# MainBoard.net
KiCad netlist of a schematic drawn in EAGLE
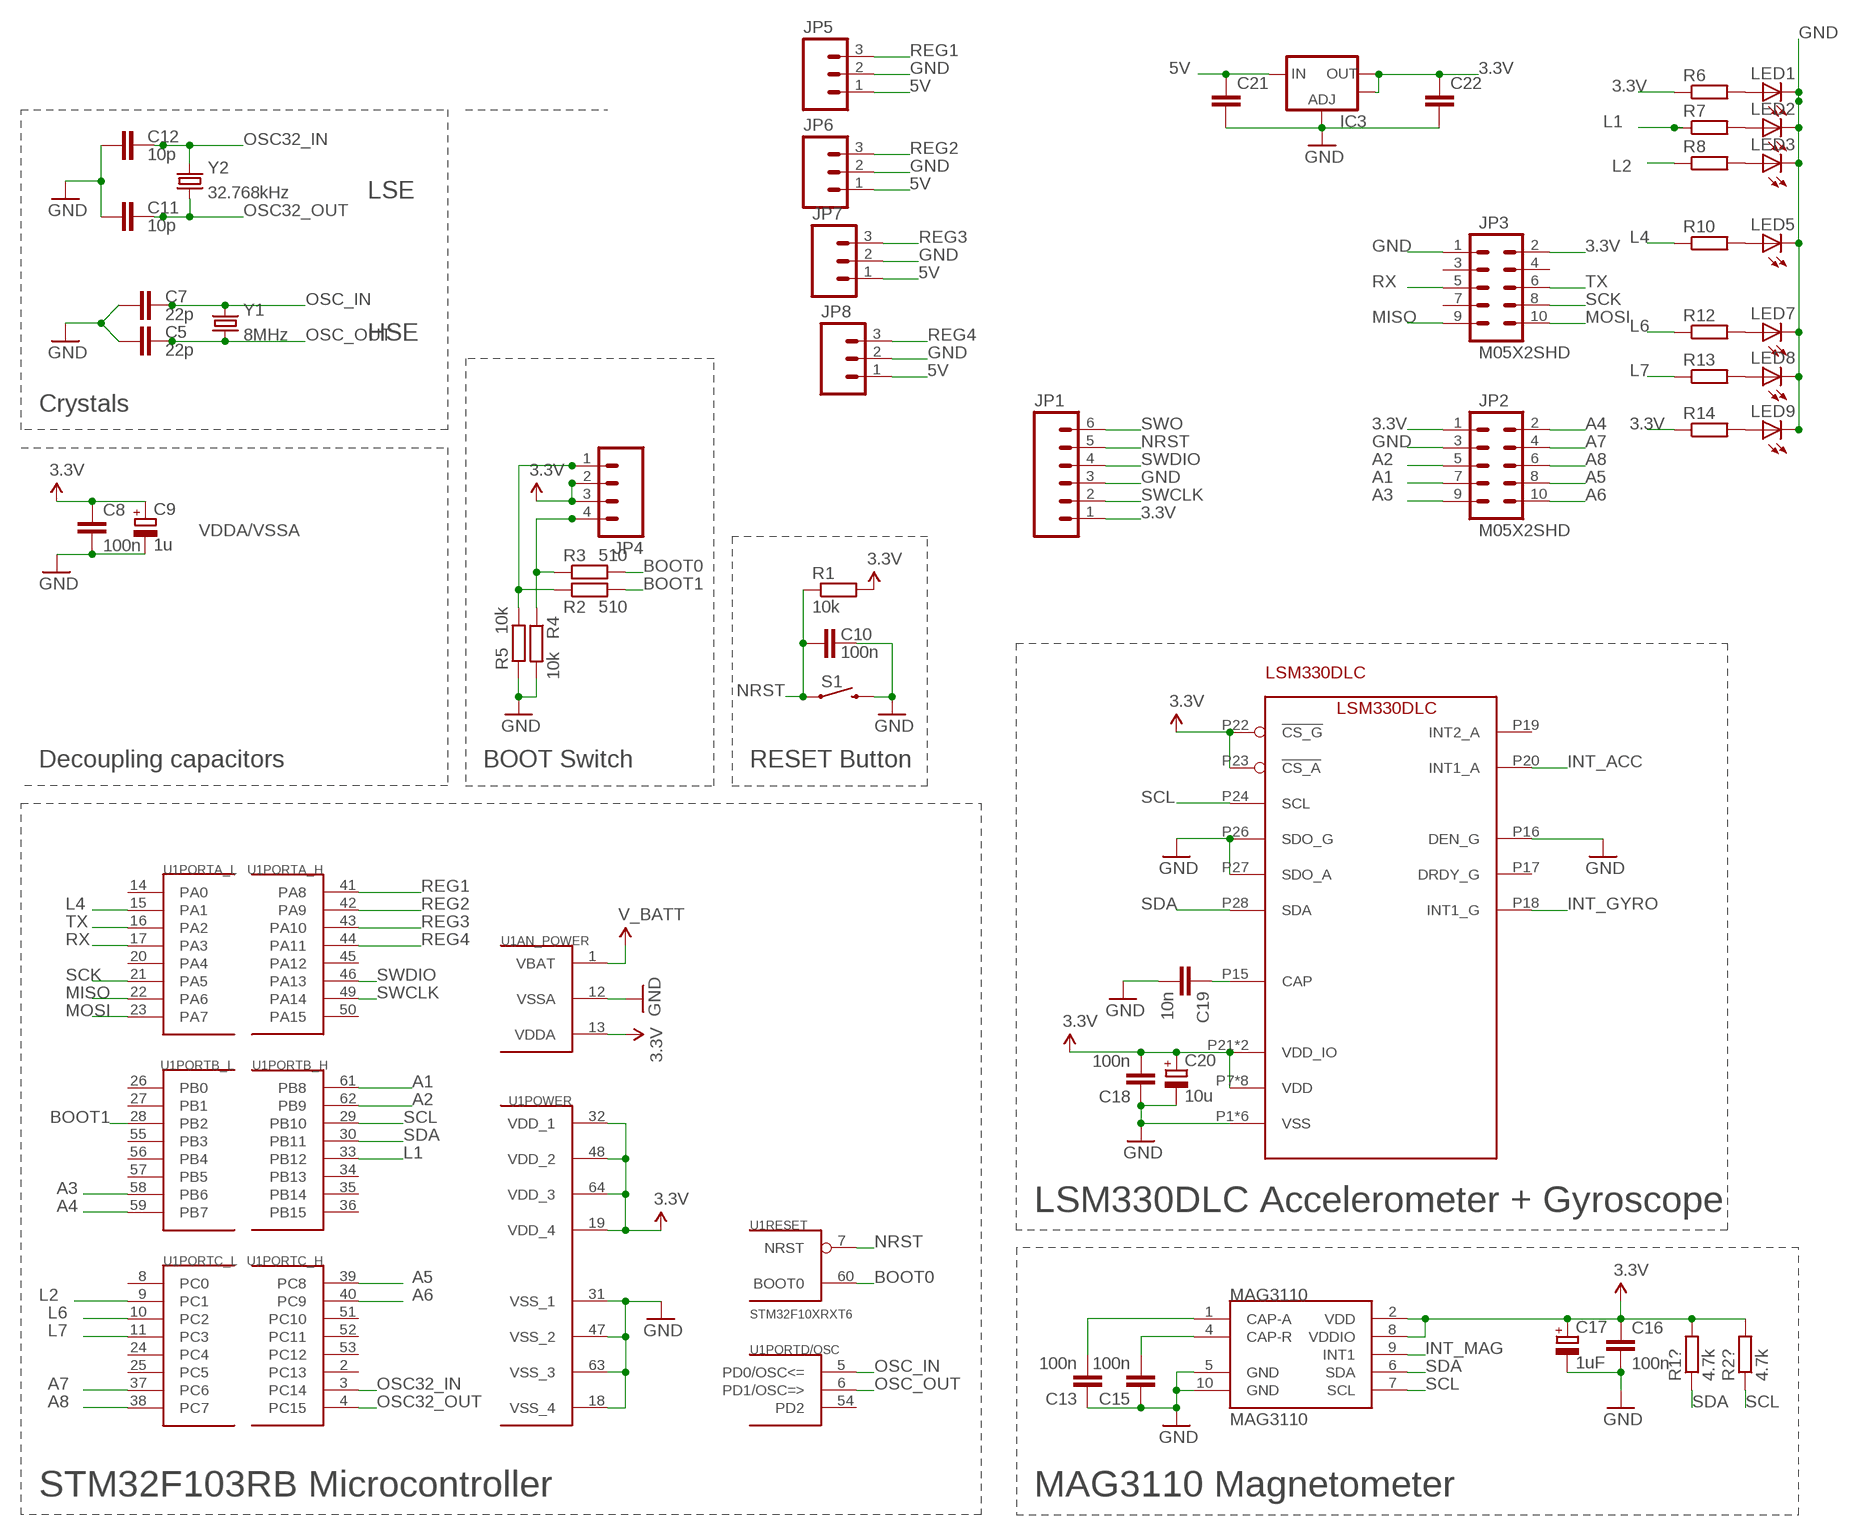
[diagram p0: schematic, sheet 1]

(export (version "E")
  (design (tool "Eeschema 10.0.6"))
  (components
    (comp (ref "C5")
      (value "22p")
      (footprint "eagle-import:C0805")
      (libsource (lib "eagle-import") (part "C-EUC0805"))
    )
    (comp (ref "C7")
      (value "22p")
      (footprint "eagle-import:C0805")
      (libsource (lib "eagle-import") (part "C-EUC0805"))
    )
    (comp (ref "C8")
      (value "100n")
      (footprint "eagle-import:C0805")
      (libsource (lib "eagle-import") (part "C-EUC0805"))
    )
    (comp (ref "C9")
      (value "1u")
      (footprint "eagle-import:SMC_A")
      (libsource (lib "eagle-import") (part "CPOL-EUSMCA"))
    )
    (comp (ref "C10")
      (value "100n")
      (footprint "eagle-import:C0805")
      (libsource (lib "eagle-import") (part "C-EUC0805"))
    )
    (comp (ref "C11")
      (value "10p")
      (footprint "eagle-import:C0805")
      (libsource (lib "eagle-import") (part "C-EUC0805"))
    )
    (comp (ref "C12")
      (value "10p")
      (footprint "eagle-import:C0805")
      (libsource (lib "eagle-import") (part "C-EUC0805"))
    )
    (comp (ref "C13")
      (value "100n")
      (footprint "eagle-import:C0805")
      (libsource (lib "eagle-import") (part "C-EUC0805"))
    )
    (comp (ref "C15")
      (value "100n")
      (footprint "eagle-import:C0805")
      (libsource (lib "eagle-import") (part "C-EUC0805"))
    )
    (comp (ref "C16")
      (value "100n")
      (footprint "eagle-import:C0805")
      (libsource (lib "eagle-import") (part "C-EUC0805"))
    )
    (comp (ref "C17")
      (value "1uF")
      (footprint "eagle-import:SMC_A")
      (libsource (lib "eagle-import") (part "CPOL-EUSMCA"))
    )
    (comp (ref "C18")
      (value "100n")
      (footprint "eagle-import:C0805")
      (libsource (lib "eagle-import") (part "resistor_C-EUC0805"))
    )
    (comp (ref "C19")
      (value "10n")
      (footprint "eagle-import:C0805")
      (libsource (lib "eagle-import") (part "resistor_C-EUC0805"))
    )
    (comp (ref "C20")
      (value "10u")
      (footprint "eagle-import:SMC_A")
      (libsource (lib "eagle-import") (part "CPOL-EUSMCA"))
    )
    (comp (ref "C21")
      (value "C-EUC0805")
      (footprint "eagle-import:C0805")
      (libsource (lib "eagle-import") (part "C-EUC0805"))
    )
    (comp (ref "C22")
      (value "C-EUC0805")
      (footprint "eagle-import:C0805")
      (libsource (lib "eagle-import") (part "C-EUC0805"))
    )
    (comp (ref "IC3")
      (value "V_REG_LM1117SOT223")
      (footprint "eagle-import:SOT223")
      (libsource (lib "eagle-import") (part "V_REG_LM1117SOT223"))
    )
    (comp (ref "JP1")
      (value "M06LONGPADS")
      (footprint "eagle-import:1X06_LONGPADS")
      (libsource (lib "eagle-import") (part "M06LONGPADS"))
    )
    (comp (ref "JP2")
      (value "M05X2SHD")
      (footprint "eagle-import:2X5-SHROUDED")
      (libsource (lib "eagle-import") (part "M05X2SHD"))
    )
    (comp (ref "JP3")
      (value "M05X2SHD")
      (footprint "eagle-import:2X5-SHROUDED")
      (libsource (lib "eagle-import") (part "M05X2SHD"))
    )
    (comp (ref "JP4")
      (value "M04LONGPADS")
      (footprint "eagle-import:1X04_LONGPADS")
      (libsource (lib "eagle-import") (part "M04LONGPADS"))
    )
    (comp (ref "JP5")
      (value "M03LONGPADS")
      (footprint "eagle-import:1X03_LONGPADS")
      (libsource (lib "eagle-import") (part "M03LONGPADS"))
    )
    (comp (ref "JP6")
      (value "M03LONGPADS")
      (footprint "eagle-import:1X03_LONGPADS")
      (libsource (lib "eagle-import") (part "M03LONGPADS"))
    )
    (comp (ref "JP7")
      (value "M03LONGPADS")
      (footprint "eagle-import:1X03_LONGPADS")
      (libsource (lib "eagle-import") (part "M03LONGPADS"))
    )
    (comp (ref "JP8")
      (value "M03LONGPADS")
      (footprint "eagle-import:1X03_LONGPADS")
      (libsource (lib "eagle-import") (part "M03LONGPADS"))
    )
    (comp (ref "LED1")
      (value "LEDCHIPLED_0805")
      (footprint "eagle-import:CHIPLED_0805")
      (libsource (lib "eagle-import") (part "LEDCHIPLED_0805"))
    )
    (comp (ref "LED2")
      (value "LEDCHIPLED_0805")
      (footprint "eagle-import:CHIPLED_0805")
      (libsource (lib "eagle-import") (part "LEDCHIPLED_0805"))
    )
    (comp (ref "LED3")
      (value "LEDCHIPLED_0805")
      (footprint "eagle-import:CHIPLED_0805")
      (libsource (lib "eagle-import") (part "LEDCHIPLED_0805"))
    )
    (comp (ref "LED5")
      (value "LEDCHIPLED_0805")
      (footprint "eagle-import:CHIPLED_0805")
      (libsource (lib "eagle-import") (part "LEDCHIPLED_0805"))
    )
    (comp (ref "LED7")
      (value "LEDCHIPLED_0805")
      (footprint "eagle-import:CHIPLED_0805")
      (libsource (lib "eagle-import") (part "LEDCHIPLED_0805"))
    )
    (comp (ref "LED8")
      (value "LEDCHIPLED_0805")
      (footprint "eagle-import:CHIPLED_0805")
      (libsource (lib "eagle-import") (part "LEDCHIPLED_0805"))
    )
    (comp (ref "LED9")
      (value "LEDCHIPLED_0805")
      (footprint "eagle-import:CHIPLED_0805")
      (libsource (lib "eagle-import") (part "LEDCHIPLED_0805"))
    )
    (comp (ref "LSM330DLC")
      (value "LSM330DLC")
      (footprint "eagle-import:LGA_4X5X1P1_28L")
      (libsource (lib "eagle-import") (part "LSM330DLC"))
    )
    (comp (ref "MAG3110")
      (value "MAG3110")
      (footprint "eagle-import:DFN-10")
      (libsource (lib "eagle-import") (part "MAG3110"))
    )
    (comp (ref "R1")
      (value "10k")
      (footprint "eagle-import:R0805")
      (libsource (lib "eagle-import") (part "R-EU_R0805"))
    )
    (comp (ref "R1?")
      (value "4.7k")
      (footprint "eagle-import:R0805")
      (libsource (lib "eagle-import") (part "R-EU_R0805"))
    )
    (comp (ref "R2")
      (value "510")
      (footprint "eagle-import:R0805")
      (libsource (lib "eagle-import") (part "R-EU_R0805"))
    )
    (comp (ref "R2?")
      (value "4.7k")
      (footprint "eagle-import:R0805")
      (libsource (lib "eagle-import") (part "R-EU_R0805"))
    )
    (comp (ref "R3")
      (value "510")
      (footprint "eagle-import:R0805")
      (libsource (lib "eagle-import") (part "R-EU_R0805"))
    )
    (comp (ref "R4")
      (value "10k")
      (footprint "eagle-import:R0805")
      (libsource (lib "eagle-import") (part "R-EU_R0805"))
    )
    (comp (ref "R5")
      (value "10k")
      (footprint "eagle-import:R0805")
      (libsource (lib "eagle-import") (part "R-EU_R0805"))
    )
    (comp (ref "R6")
      (value "R-EU_M0805")
      (footprint "eagle-import:M0805")
      (libsource (lib "eagle-import") (part "resistor_R-EU_M0805"))
    )
    (comp (ref "R7")
      (value "R-EU_M0805")
      (footprint "eagle-import:M0805")
      (libsource (lib "eagle-import") (part "resistor_R-EU_M0805"))
    )
    (comp (ref "R8")
      (value "R-EU_M0805")
      (footprint "eagle-import:M0805")
      (libsource (lib "eagle-import") (part "resistor_R-EU_M0805"))
    )
    (comp (ref "R10")
      (value "R-EU_M0805")
      (footprint "eagle-import:M0805")
      (libsource (lib "eagle-import") (part "resistor_R-EU_M0805"))
    )
    (comp (ref "R12")
      (value "R-EU_M0805")
      (footprint "eagle-import:M0805")
      (libsource (lib "eagle-import") (part "resistor_R-EU_M0805"))
    )
    (comp (ref "R13")
      (value "R-EU_M0805")
      (footprint "eagle-import:M0805")
      (libsource (lib "eagle-import") (part "resistor_R-EU_M0805"))
    )
    (comp (ref "R14")
      (value "R-EU_M0805")
      (footprint "eagle-import:M0805")
      (libsource (lib "eagle-import") (part "resistor_R-EU_M0805"))
    )
    (comp (ref "S1")
      (value "SWITCH-MOMENTARY-2-SMD-1101NE")
      (footprint "eagle-import:TACTILE-SWITCH-1101NE")
      (libsource (lib "eagle-import") (part "SWITCH-MOMENTARY-2-SMD-1101NE"))
    )
    (comp (ref "U1")
      (value "STM32F10XRXT6")
      (footprint "eagle-import:TQFP64")
      (libsource (lib "eagle-import") (part "STM32F10XRXT6"))
    )
    (comp (ref "Y1")
      (value "8MHz")
      (footprint "eagle-import:HC49UP")
      (libsource (lib "eagle-import") (part "CRYSTALSMD"))
    )
    (comp (ref "Y2")
      (value "32.768kHz")
      (footprint "eagle-import:CRYSTAL-32KHZ-SMD_EPSON_MC146")
      (libsource (lib "eagle-import") (part "CRYSTALEPSONMC146"))
    )
  )
  (nets
    (net (code "1") (name "/5V") (class "Default")
      (node (ref "C21") (pin "1") (pinfunction "1_1") (pintype "passive"))
      (node (ref "IC3") (pin "3") (pinfunction "IN_3") (pintype "input"))
      (node (ref "JP5") (pin "1") (pinfunction "1_1") (pintype "passive"))
      (node (ref "JP6") (pin "1") (pinfunction "1_1") (pintype "passive"))
      (node (ref "JP7") (pin "1") (pinfunction "1_1") (pintype "passive"))
      (node (ref "JP8") (pin "1") (pinfunction "1_1") (pintype "passive"))
    )
    (net (code "2") (name "/A1") (class "Default")
      (node (ref "JP2") (pin "7") (pinfunction "7_7") (pintype "passive"))
      (node (ref "U1") (pin "61") (pinfunction "PB8_61") (pintype "bidirectional"))
    )
    (net (code "3") (name "/A2") (class "Default")
      (node (ref "JP2") (pin "5") (pinfunction "5_5") (pintype "passive"))
      (node (ref "U1") (pin "62") (pinfunction "PB9_62") (pintype "bidirectional"))
    )
    (net (code "4") (name "/A3") (class "Default")
      (node (ref "JP2") (pin "9") (pinfunction "9_9") (pintype "passive"))
      (node (ref "U1") (pin "58") (pinfunction "PB6_58") (pintype "bidirectional"))
    )
    (net (code "5") (name "/A4") (class "Default")
      (node (ref "JP2") (pin "2") (pinfunction "2_2") (pintype "passive"))
      (node (ref "U1") (pin "59") (pinfunction "PB7_59") (pintype "bidirectional"))
    )
    (net (code "6") (name "/A5") (class "Default")
      (node (ref "JP2") (pin "8") (pinfunction "8_8") (pintype "passive"))
      (node (ref "U1") (pin "39") (pinfunction "PC8_39") (pintype "bidirectional"))
    )
    (net (code "7") (name "/A6") (class "Default")
      (node (ref "JP2") (pin "10") (pinfunction "10_10") (pintype "passive"))
      (node (ref "U1") (pin "40") (pinfunction "PC9_40") (pintype "bidirectional"))
    )
    (net (code "8") (name "/A7") (class "Default")
      (node (ref "JP2") (pin "4") (pinfunction "4_4") (pintype "passive"))
      (node (ref "U1") (pin "37") (pinfunction "PC6_37") (pintype "bidirectional"))
    )
    (net (code "9") (name "/A8") (class "Default")
      (node (ref "JP2") (pin "6") (pinfunction "6_6") (pintype "passive"))
      (node (ref "U1") (pin "38") (pinfunction "PC7_38") (pintype "bidirectional"))
    )
    (net (code "10") (name "/BOOT0") (class "Default")
      (node (ref "R3") (pin "2") (pinfunction "2_2") (pintype "passive"))
      (node (ref "U1") (pin "60") (pinfunction "BOOT0_60") (pintype "input"))
    )
    (net (code "11") (name "/BOOT1") (class "Default")
      (node (ref "R2") (pin "2") (pinfunction "2_2") (pintype "passive"))
      (node (ref "U1") (pin "28") (pinfunction "PB2_28") (pintype "bidirectional"))
    )
    (net (code "12") (name "/INT_ACC") (class "Default")
      (node (ref "LSM330DLC") (pin "P20") (pinfunction "INT1_A_P20") (pintype "output"))
    )
    (net (code "13") (name "/INT_GYRO") (class "Default")
      (node (ref "LSM330DLC") (pin "P18") (pinfunction "INT1_G_P18") (pintype "output"))
    )
    (net (code "14") (name "/INT_MAG") (class "Default")
      (node (ref "MAG3110") (pin "9") (pinfunction "INT1_9") (pintype "bidirectional"))
    )
    (net (code "15") (name "/L1") (class "Default")
      (node (ref "R7") (pin "1") (pinfunction "1_1") (pintype "passive"))
      (node (ref "U1") (pin "33") (pinfunction "PB12_33") (pintype "bidirectional"))
    )
    (net (code "16") (name "/L2") (class "Default")
      (node (ref "R8") (pin "1") (pinfunction "1_1") (pintype "passive"))
      (node (ref "U1") (pin "9") (pinfunction "PC1_9") (pintype "bidirectional"))
    )
    (net (code "17") (name "/L4") (class "Default")
      (node (ref "R10") (pin "1") (pinfunction "1_1") (pintype "passive"))
      (node (ref "U1") (pin "15") (pinfunction "PA1_15") (pintype "bidirectional"))
    )
    (net (code "18") (name "/L6") (class "Default")
      (node (ref "R12") (pin "1") (pinfunction "1_1") (pintype "passive"))
      (node (ref "U1") (pin "10") (pinfunction "PC2_10") (pintype "bidirectional"))
    )
    (net (code "19") (name "/L7") (class "Default")
      (node (ref "R13") (pin "1") (pinfunction "1_1") (pintype "passive"))
      (node (ref "U1") (pin "11") (pinfunction "PC3_11") (pintype "bidirectional"))
    )
    (net (code "20") (name "/MISO") (class "Default")
      (node (ref "JP3") (pin "9") (pinfunction "9_9") (pintype "passive"))
      (node (ref "U1") (pin "22") (pinfunction "PA6_22") (pintype "bidirectional"))
    )
    (net (code "21") (name "/MOSI") (class "Default")
      (node (ref "JP3") (pin "10") (pinfunction "10_10") (pintype "passive"))
      (node (ref "U1") (pin "23") (pinfunction "PA7_23") (pintype "bidirectional"))
    )
    (net (code "22") (name "/NRST") (class "Default")
      (node (ref "C10") (pin "1") (pinfunction "1_1") (pintype "passive"))
      (node (ref "JP1") (pin "5") (pinfunction "5_5") (pintype "passive"))
      (node (ref "R1") (pin "1") (pinfunction "1_1") (pintype "passive"))
      (node (ref "S1") (pin "P$1") (pinfunction "1_P$1") (pintype "passive"))
      (node (ref "U1") (pin "7") (pinfunction "NRST_7") (pintype "input"))
    )
    (net (code "23") (name "/OSC32_IN") (class "Default")
      (node (ref "C12") (pin "2") (pinfunction "2_2") (pintype "passive"))
      (node (ref "U1") (pin "3") (pinfunction "PC14_3") (pintype "bidirectional"))
      (node (ref "Y2") (pin "P$1") (pinfunction "2_P$1") (pintype "passive"))
    )
    (net (code "24") (name "/OSC32_OUT") (class "Default")
      (node (ref "C11") (pin "2") (pinfunction "2_2") (pintype "passive"))
      (node (ref "U1") (pin "4") (pinfunction "PC15_4") (pintype "bidirectional"))
      (node (ref "Y2") (pin "P$2") (pinfunction "1_P$2") (pintype "passive"))
    )
    (net (code "25") (name "/OSC_IN") (class "Default")
      (node (ref "C7") (pin "2") (pinfunction "2_2") (pintype "passive"))
      (node (ref "U1") (pin "5") (pinfunction "PD0/OSC<=_5") (pintype "bidirectional"))
      (node (ref "Y1") (pin "2") (pinfunction "2_2") (pintype "passive"))
    )
    (net (code "26") (name "/OSC_OUT") (class "Default")
      (node (ref "C5") (pin "2") (pinfunction "2_2") (pintype "passive"))
      (node (ref "U1") (pin "6") (pinfunction "PD1/OSC=>_6") (pintype "bidirectional"))
      (node (ref "Y1") (pin "1") (pinfunction "1_1") (pintype "passive"))
    )
    (net (code "27") (name "/REG1") (class "Default")
      (node (ref "JP5") (pin "3") (pinfunction "3_3") (pintype "passive"))
      (node (ref "U1") (pin "41") (pinfunction "PA8_41") (pintype "bidirectional"))
    )
    (net (code "28") (name "/REG2") (class "Default")
      (node (ref "JP6") (pin "3") (pinfunction "3_3") (pintype "passive"))
      (node (ref "U1") (pin "42") (pinfunction "PA9_42") (pintype "bidirectional"))
    )
    (net (code "29") (name "/REG3") (class "Default")
      (node (ref "JP7") (pin "3") (pinfunction "3_3") (pintype "passive"))
      (node (ref "U1") (pin "43") (pinfunction "PA10_43") (pintype "bidirectional"))
    )
    (net (code "30") (name "/REG4") (class "Default")
      (node (ref "JP8") (pin "3") (pinfunction "3_3") (pintype "passive"))
      (node (ref "U1") (pin "44") (pinfunction "PA11_44") (pintype "bidirectional"))
    )
    (net (code "31") (name "/RX") (class "Default")
      (node (ref "JP3") (pin "5") (pinfunction "5_5") (pintype "passive"))
      (node (ref "U1") (pin "17") (pinfunction "PA3_17") (pintype "bidirectional"))
    )
    (net (code "32") (name "/SCK") (class "Default")
      (node (ref "JP3") (pin "8") (pinfunction "8_8") (pintype "passive"))
      (node (ref "U1") (pin "21") (pinfunction "PA5_21") (pintype "bidirectional"))
    )
    (net (code "33") (name "/SCL") (class "Default")
      (node (ref "LSM330DLC") (pin "P24") (pinfunction "SCL_P24") (pintype "input"))
      (node (ref "MAG3110") (pin "7") (pinfunction "SCL_7") (pintype "bidirectional"))
      (node (ref "R2?") (pin "1") (pinfunction "1_1") (pintype "passive"))
      (node (ref "U1") (pin "29") (pinfunction "PB10_29") (pintype "bidirectional"))
    )
    (net (code "34") (name "/SDA") (class "Default")
      (node (ref "LSM330DLC") (pin "P28") (pinfunction "SDA_P28") (pintype "input"))
      (node (ref "MAG3110") (pin "6") (pinfunction "SDA_6") (pintype "bidirectional"))
      (node (ref "R1?") (pin "1") (pinfunction "1_1") (pintype "passive"))
      (node (ref "U1") (pin "30") (pinfunction "PB11_30") (pintype "bidirectional"))
    )
    (net (code "35") (name "/SWCLK") (class "Default")
      (node (ref "JP1") (pin "2") (pinfunction "2_2") (pintype "passive"))
      (node (ref "U1") (pin "49") (pinfunction "PA14_49") (pintype "bidirectional"))
    )
    (net (code "36") (name "/SWDIO") (class "Default")
      (node (ref "JP1") (pin "4") (pinfunction "4_4") (pintype "passive"))
      (node (ref "U1") (pin "46") (pinfunction "PA13_46") (pintype "bidirectional"))
    )
    (net (code "37") (name "/SWO") (class "Default")
      (node (ref "JP1") (pin "6") (pinfunction "6_6") (pintype "passive"))
    )
    (net (code "38") (name "/TX") (class "Default")
      (node (ref "JP3") (pin "6") (pinfunction "6_6") (pintype "passive"))
      (node (ref "U1") (pin "16") (pinfunction "PA2_16") (pintype "bidirectional"))
    )
    (net (code "39") (name "3.3V") (class "Default")
      (node (ref "C16") (pin "1") (pinfunction "1_1") (pintype "passive"))
      (node (ref "C17") (pin "+") (pinfunction "+_+") (pintype "passive"))
      (node (ref "C18") (pin "2") (pinfunction "2_2") (pintype "passive"))
      (node (ref "C20") (pin "+") (pinfunction "+_+") (pintype "passive"))
      (node (ref "C22") (pin "1") (pinfunction "1_1") (pintype "passive"))
      (node (ref "C8") (pin "1") (pinfunction "1_1") (pintype "passive"))
      (node (ref "C9") (pin "+") (pinfunction "+_+") (pintype "passive"))
      (node (ref "IC3") (pin "2") (pinfunction "OUT_2") (pintype "output"))
      (node (ref "IC3") (pin "4") (pinfunction "OUT_4") (pintype "output"))
      (node (ref "JP1") (pin "1") (pinfunction "1_1") (pintype "passive"))
      (node (ref "JP2") (pin "1") (pinfunction "1_1") (pintype "passive"))
      (node (ref "JP3") (pin "2") (pinfunction "2_2") (pintype "passive"))
      (node (ref "JP4") (pin "2") (pinfunction "2_2") (pintype "passive"))
      (node (ref "JP4") (pin "3") (pinfunction "3_3") (pintype "passive"))
      (node (ref "LSM330DLC") (pin "P10") (pinfunction "VDD_P10") (pintype "power_in"))
      (node (ref "LSM330DLC") (pin "P11") (pinfunction "VDD_P11") (pintype "power_in"))
      (node (ref "LSM330DLC") (pin "P12") (pinfunction "VDD_P12") (pintype "power_in"))
      (node (ref "LSM330DLC") (pin "P13") (pinfunction "VDD_P13") (pintype "power_in"))
      (node (ref "LSM330DLC") (pin "P14") (pinfunction "VDD_P14") (pintype "power_in"))
      (node (ref "LSM330DLC") (pin "P21") (pinfunction "VDD_IO_P21") (pintype "power_in"))
      (node (ref "LSM330DLC") (pin "P22") (pinfunction "~{CS_G}_P22") (pintype "input"))
      (node (ref "LSM330DLC") (pin "P23") (pinfunction "~{CS_A}_P23") (pintype "input"))
      (node (ref "LSM330DLC") (pin "P25") (pinfunction "VDD_IO_P25") (pintype "power_in"))
      (node (ref "LSM330DLC") (pin "P7") (pinfunction "VDD_P7") (pintype "power_in"))
      (node (ref "LSM330DLC") (pin "P8") (pinfunction "VDD_P8") (pintype "power_in"))
      (node (ref "LSM330DLC") (pin "P9") (pinfunction "VDD_P9") (pintype "power_in"))
      (node (ref "MAG3110") (pin "2") (pinfunction "VDD_2") (pintype "bidirectional"))
      (node (ref "MAG3110") (pin "8") (pinfunction "VDDIO_8") (pintype "bidirectional"))
      (node (ref "R1") (pin "2") (pinfunction "2_2") (pintype "passive"))
      (node (ref "R14") (pin "1") (pinfunction "1_1") (pintype "passive"))
      (node (ref "R1?") (pin "2") (pinfunction "2_2") (pintype "passive"))
      (node (ref "R2?") (pin "2") (pinfunction "2_2") (pintype "passive"))
      (node (ref "R6") (pin "1") (pinfunction "1_1") (pintype "passive"))
      (node (ref "U1") (pin "13") (pinfunction "VDDA_13") (pintype "power_in"))
      (node (ref "U1") (pin "19") (pinfunction "VDD_4_19") (pintype "power_in"))
      (node (ref "U1") (pin "32") (pinfunction "VDD_1_32") (pintype "power_in"))
      (node (ref "U1") (pin "48") (pinfunction "VDD_2_48") (pintype "power_in"))
      (node (ref "U1") (pin "64") (pinfunction "VDD_3_64") (pintype "power_in"))
    )
    (net (code "40") (name "GND") (class "Default")
      (node (ref "C10") (pin "2") (pinfunction "2_2") (pintype "passive"))
      (node (ref "C11") (pin "1") (pinfunction "1_1") (pintype "passive"))
      (node (ref "C12") (pin "1") (pinfunction "1_1") (pintype "passive"))
      (node (ref "C13") (pin "1") (pinfunction "1_1") (pintype "passive"))
      (node (ref "C15") (pin "1") (pinfunction "1_1") (pintype "passive"))
      (node (ref "C16") (pin "2") (pinfunction "2_2") (pintype "passive"))
      (node (ref "C17") (pin "-") (pinfunction "-_-") (pintype "passive"))
      (node (ref "C18") (pin "1") (pinfunction "1_1") (pintype "passive"))
      (node (ref "C19") (pin "2") (pinfunction "2_2") (pintype "passive"))
      (node (ref "C20") (pin "-") (pinfunction "-_-") (pintype "passive"))
      (node (ref "C21") (pin "2") (pinfunction "2_2") (pintype "passive"))
      (node (ref "C22") (pin "2") (pinfunction "2_2") (pintype "passive"))
      (node (ref "C5") (pin "1") (pinfunction "1_1") (pintype "passive"))
      (node (ref "C7") (pin "1") (pinfunction "1_1") (pintype "passive"))
      (node (ref "C8") (pin "2") (pinfunction "2_2") (pintype "passive"))
      (node (ref "C9") (pin "-") (pinfunction "-_-") (pintype "passive"))
      (node (ref "IC3") (pin "1") (pinfunction "ADJ_1") (pintype "input"))
      (node (ref "JP1") (pin "3") (pinfunction "3_3") (pintype "passive"))
      (node (ref "JP2") (pin "3") (pinfunction "3_3") (pintype "passive"))
      (node (ref "JP3") (pin "1") (pinfunction "1_1") (pintype "passive"))
      (node (ref "JP5") (pin "2") (pinfunction "2_2") (pintype "passive"))
      (node (ref "JP6") (pin "2") (pinfunction "2_2") (pintype "passive"))
      (node (ref "JP7") (pin "2") (pinfunction "2_2") (pintype "passive"))
      (node (ref "JP8") (pin "2") (pinfunction "2_2") (pintype "passive"))
      (node (ref "LED1") (pin "C") (pinfunction "C_C") (pintype "passive"))
      (node (ref "LED2") (pin "C") (pinfunction "C_C") (pintype "passive"))
      (node (ref "LED3") (pin "C") (pinfunction "C_C") (pintype "passive"))
      (node (ref "LED5") (pin "C") (pinfunction "C_C") (pintype "passive"))
      (node (ref "LED7") (pin "C") (pinfunction "C_C") (pintype "passive"))
      (node (ref "LED8") (pin "C") (pinfunction "C_C") (pintype "passive"))
      (node (ref "LED9") (pin "C") (pinfunction "C_C") (pintype "passive"))
      (node (ref "LSM330DLC") (pin "P1") (pinfunction "VSS_P1") (pintype "power_in"))
      (node (ref "LSM330DLC") (pin "P16") (pinfunction "DEN_G_P16") (pintype "input"))
      (node (ref "LSM330DLC") (pin "P2") (pinfunction "VSS_P2") (pintype "power_in"))
      (node (ref "LSM330DLC") (pin "P26") (pinfunction "SDO_G_P26") (pintype "output"))
      (node (ref "LSM330DLC") (pin "P27") (pinfunction "SDO_A_P27") (pintype "output"))
      (node (ref "LSM330DLC") (pin "P3") (pinfunction "VSS_P3") (pintype "power_in"))
      (node (ref "LSM330DLC") (pin "P4") (pinfunction "VSS_P4") (pintype "power_in"))
      (node (ref "LSM330DLC") (pin "P5") (pinfunction "VSS_P5") (pintype "power_in"))
      (node (ref "LSM330DLC") (pin "P6") (pinfunction "VSS_P6") (pintype "power_in"))
      (node (ref "MAG3110") (pin "10") (pinfunction "GND_10") (pintype "bidirectional"))
      (node (ref "MAG3110") (pin "5") (pinfunction "GND_5") (pintype "bidirectional"))
      (node (ref "R4") (pin "2") (pinfunction "2_2") (pintype "passive"))
      (node (ref "R5") (pin "1") (pinfunction "1_1") (pintype "passive"))
      (node (ref "S1") (pin "P$2") (pinfunction "2_P$2") (pintype "passive"))
      (node (ref "U1") (pin "12") (pinfunction "VSSA_12") (pintype "power_in"))
      (node (ref "U1") (pin "18") (pinfunction "VSS_4_18") (pintype "power_in"))
      (node (ref "U1") (pin "31") (pinfunction "VSS_1_31") (pintype "power_in"))
      (node (ref "U1") (pin "47") (pinfunction "VSS_2_47") (pintype "power_in"))
      (node (ref "U1") (pin "63") (pinfunction "VSS_3_63") (pintype "power_in"))
    )
    (net (code "41") (name "Net-(JP4-Pad1)") (class "Default")
      (node (ref "JP4") (pin "1") (pinfunction "1_1") (pintype "passive"))
      (node (ref "R2") (pin "1") (pinfunction "1_1") (pintype "passive"))
      (node (ref "R5") (pin "2") (pinfunction "2_2") (pintype "passive"))
    )
    (net (code "42") (name "Net-(JP4-Pad4)") (class "Default")
      (node (ref "JP4") (pin "4") (pinfunction "4_4") (pintype "passive"))
      (node (ref "R3") (pin "1") (pinfunction "1_1") (pintype "passive"))
      (node (ref "R4") (pin "1") (pinfunction "1_1") (pintype "passive"))
    )
    (net (code "43") (name "Net-(LED1-PadA)") (class "Default")
      (node (ref "LED1") (pin "A") (pinfunction "A_A") (pintype "passive"))
      (node (ref "R6") (pin "2") (pinfunction "2_2") (pintype "passive"))
    )
    (net (code "44") (name "Net-(LED2-PadA)") (class "Default")
      (node (ref "LED2") (pin "A") (pinfunction "A_A") (pintype "passive"))
      (node (ref "R7") (pin "2") (pinfunction "2_2") (pintype "passive"))
    )
    (net (code "45") (name "Net-(LED3-PadA)") (class "Default")
      (node (ref "LED3") (pin "A") (pinfunction "A_A") (pintype "passive"))
      (node (ref "R8") (pin "2") (pinfunction "2_2") (pintype "passive"))
    )
    (net (code "46") (name "Net-(LED5-PadA)") (class "Default")
      (node (ref "LED5") (pin "A") (pinfunction "A_A") (pintype "passive"))
      (node (ref "R10") (pin "2") (pinfunction "2_2") (pintype "passive"))
    )
    (net (code "47") (name "Net-(LED7-PadA)") (class "Default")
      (node (ref "LED7") (pin "A") (pinfunction "A_A") (pintype "passive"))
      (node (ref "R12") (pin "2") (pinfunction "2_2") (pintype "passive"))
    )
    (net (code "48") (name "Net-(LED8-PadA)") (class "Default")
      (node (ref "LED8") (pin "A") (pinfunction "A_A") (pintype "passive"))
      (node (ref "R13") (pin "2") (pinfunction "2_2") (pintype "passive"))
    )
    (net (code "49") (name "Net-(LED9-PadA)") (class "Default")
      (node (ref "LED9") (pin "A") (pinfunction "A_A") (pintype "passive"))
      (node (ref "R14") (pin "2") (pinfunction "2_2") (pintype "passive"))
    )
    (net (code "50") (name "Net-(LSM330DLC-CAP)") (class "Default")
      (node (ref "C19") (pin "1") (pinfunction "1_1") (pintype "passive"))
      (node (ref "LSM330DLC") (pin "P15") (pinfunction "CAP_P15") (pintype "power_in"))
    )
    (net (code "51") (name "Net-(MAG3110-CAP-A)") (class "Default")
      (node (ref "C13") (pin "2") (pinfunction "2_2") (pintype "passive"))
      (node (ref "MAG3110") (pin "1") (pinfunction "CAP-A_1") (pintype "bidirectional"))
    )
    (net (code "52") (name "Net-(MAG3110-CAP-R)") (class "Default")
      (node (ref "C15") (pin "2") (pinfunction "2_2") (pintype "passive"))
      (node (ref "MAG3110") (pin "4") (pinfunction "CAP-R_4") (pintype "bidirectional"))
    )
    (net (code "53") (name "V_BATT") (class "Default")
      (node (ref "U1") (pin "1") (pinfunction "VBAT_1") (pintype "power_in"))
    )
    (net (code "54") (name "unconnected-(JP3-Pad3)") (class "Default")
      (node (ref "JP3") (pin "3") (pinfunction "3_3") (pintype "passive"))
    )
    (net (code "55") (name "unconnected-(JP3-Pad4)") (class "Default")
      (node (ref "JP3") (pin "4") (pinfunction "4_4") (pintype "passive"))
    )
    (net (code "56") (name "unconnected-(JP3-Pad7)") (class "Default")
      (node (ref "JP3") (pin "7") (pinfunction "7_7") (pintype "passive"))
    )
    (net (code "57") (name "unconnected-(LSM330DLC-DRDY_G-PadP17)") (class "Default")
      (node (ref "LSM330DLC") (pin "P17") (pinfunction "DRDY_G_P17") (pintype "output"))
    )
    (net (code "58") (name "unconnected-(LSM330DLC-INT2_A-PadP19)") (class "Default")
      (node (ref "LSM330DLC") (pin "P19") (pinfunction "INT2_A_P19") (pintype "output"))
    )
    (net (code "59") (name "unconnected-(U1B-PA12-Pad45)") (class "Default")
      (node (ref "U1") (pin "45") (pinfunction "PA12_45") (pintype "bidirectional"))
    )
    (net (code "60") (name "unconnected-(U1B-PA15-Pad50)") (class "Default")
      (node (ref "U1") (pin "50") (pinfunction "PA15_50") (pintype "bidirectional"))
    )
    (net (code "61") (name "unconnected-(U1C-PA0-Pad14)") (class "Default")
      (node (ref "U1") (pin "14") (pinfunction "PA0_14") (pintype "bidirectional"))
    )
    (net (code "62") (name "unconnected-(U1C-PA4-Pad20)") (class "Default")
      (node (ref "U1") (pin "20") (pinfunction "PA4_20") (pintype "bidirectional"))
    )
    (net (code "63") (name "unconnected-(U1D-PB13-Pad34)") (class "Default")
      (node (ref "U1") (pin "34") (pinfunction "PB13_34") (pintype "bidirectional"))
    )
    (net (code "64") (name "unconnected-(U1D-PB14-Pad35)") (class "Default")
      (node (ref "U1") (pin "35") (pinfunction "PB14_35") (pintype "bidirectional"))
    )
    (net (code "65") (name "unconnected-(U1D-PB15-Pad36)") (class "Default")
      (node (ref "U1") (pin "36") (pinfunction "PB15_36") (pintype "bidirectional"))
    )
    (net (code "66") (name "unconnected-(U1E-PB0-Pad26)") (class "Default")
      (node (ref "U1") (pin "26") (pinfunction "PB0_26") (pintype "bidirectional"))
    )
    (net (code "67") (name "unconnected-(U1E-PB1-Pad27)") (class "Default")
      (node (ref "U1") (pin "27") (pinfunction "PB1_27") (pintype "bidirectional"))
    )
    (net (code "68") (name "unconnected-(U1E-PB3-Pad55)") (class "Default")
      (node (ref "U1") (pin "55") (pinfunction "PB3_55") (pintype "bidirectional"))
    )
    (net (code "69") (name "unconnected-(U1E-PB4-Pad56)") (class "Default")
      (node (ref "U1") (pin "56") (pinfunction "PB4_56") (pintype "bidirectional"))
    )
    (net (code "70") (name "unconnected-(U1E-PB5-Pad57)") (class "Default")
      (node (ref "U1") (pin "57") (pinfunction "PB5_57") (pintype "bidirectional"))
    )
    (net (code "71") (name "unconnected-(U1F-PC10-Pad51)") (class "Default")
      (node (ref "U1") (pin "51") (pinfunction "PC10_51") (pintype "bidirectional"))
    )
    (net (code "72") (name "unconnected-(U1F-PC11-Pad52)") (class "Default")
      (node (ref "U1") (pin "52") (pinfunction "PC11_52") (pintype "bidirectional"))
    )
    (net (code "73") (name "unconnected-(U1F-PC12-Pad53)") (class "Default")
      (node (ref "U1") (pin "53") (pinfunction "PC12_53") (pintype "bidirectional"))
    )
    (net (code "74") (name "unconnected-(U1F-PC13-Pad2)") (class "Default")
      (node (ref "U1") (pin "2") (pinfunction "PC13_2") (pintype "bidirectional"))
    )
    (net (code "75") (name "unconnected-(U1G-PC0-Pad8)") (class "Default")
      (node (ref "U1") (pin "8") (pinfunction "PC0_8") (pintype "bidirectional"))
    )
    (net (code "76") (name "unconnected-(U1G-PC4-Pad24)") (class "Default")
      (node (ref "U1") (pin "24") (pinfunction "PC4_24") (pintype "bidirectional"))
    )
    (net (code "77") (name "unconnected-(U1G-PC5-Pad25)") (class "Default")
      (node (ref "U1") (pin "25") (pinfunction "PC5_25") (pintype "bidirectional"))
    )
    (net (code "78") (name "unconnected-(U1H-PD2-Pad54)") (class "Default")
      (node (ref "U1") (pin "54") (pinfunction "PD2_54") (pintype "bidirectional"))
    )
  )
)
